# PFC_Method_Lighting_Driver_V2.net
KiCad netlist of a schematic drawn in EAGLE
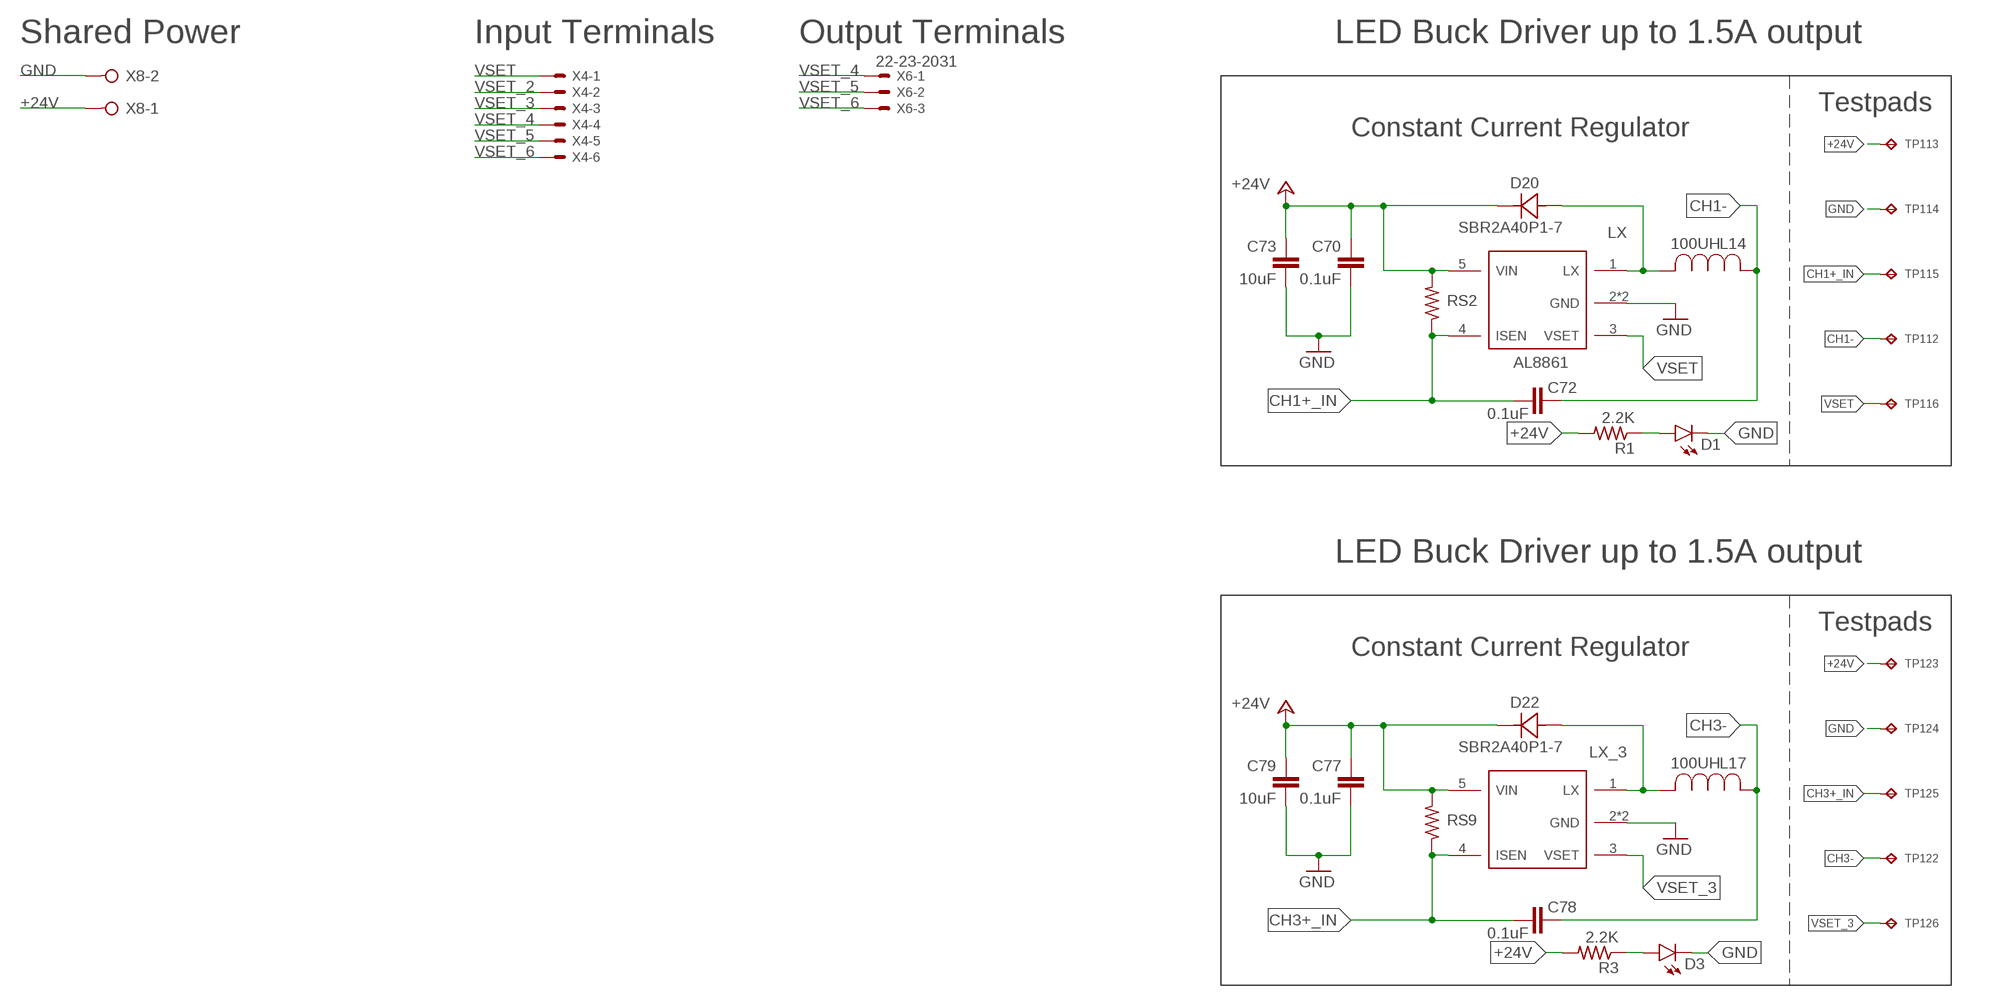
[diagram p0: schematic, sheet 1, part 1 of 2]
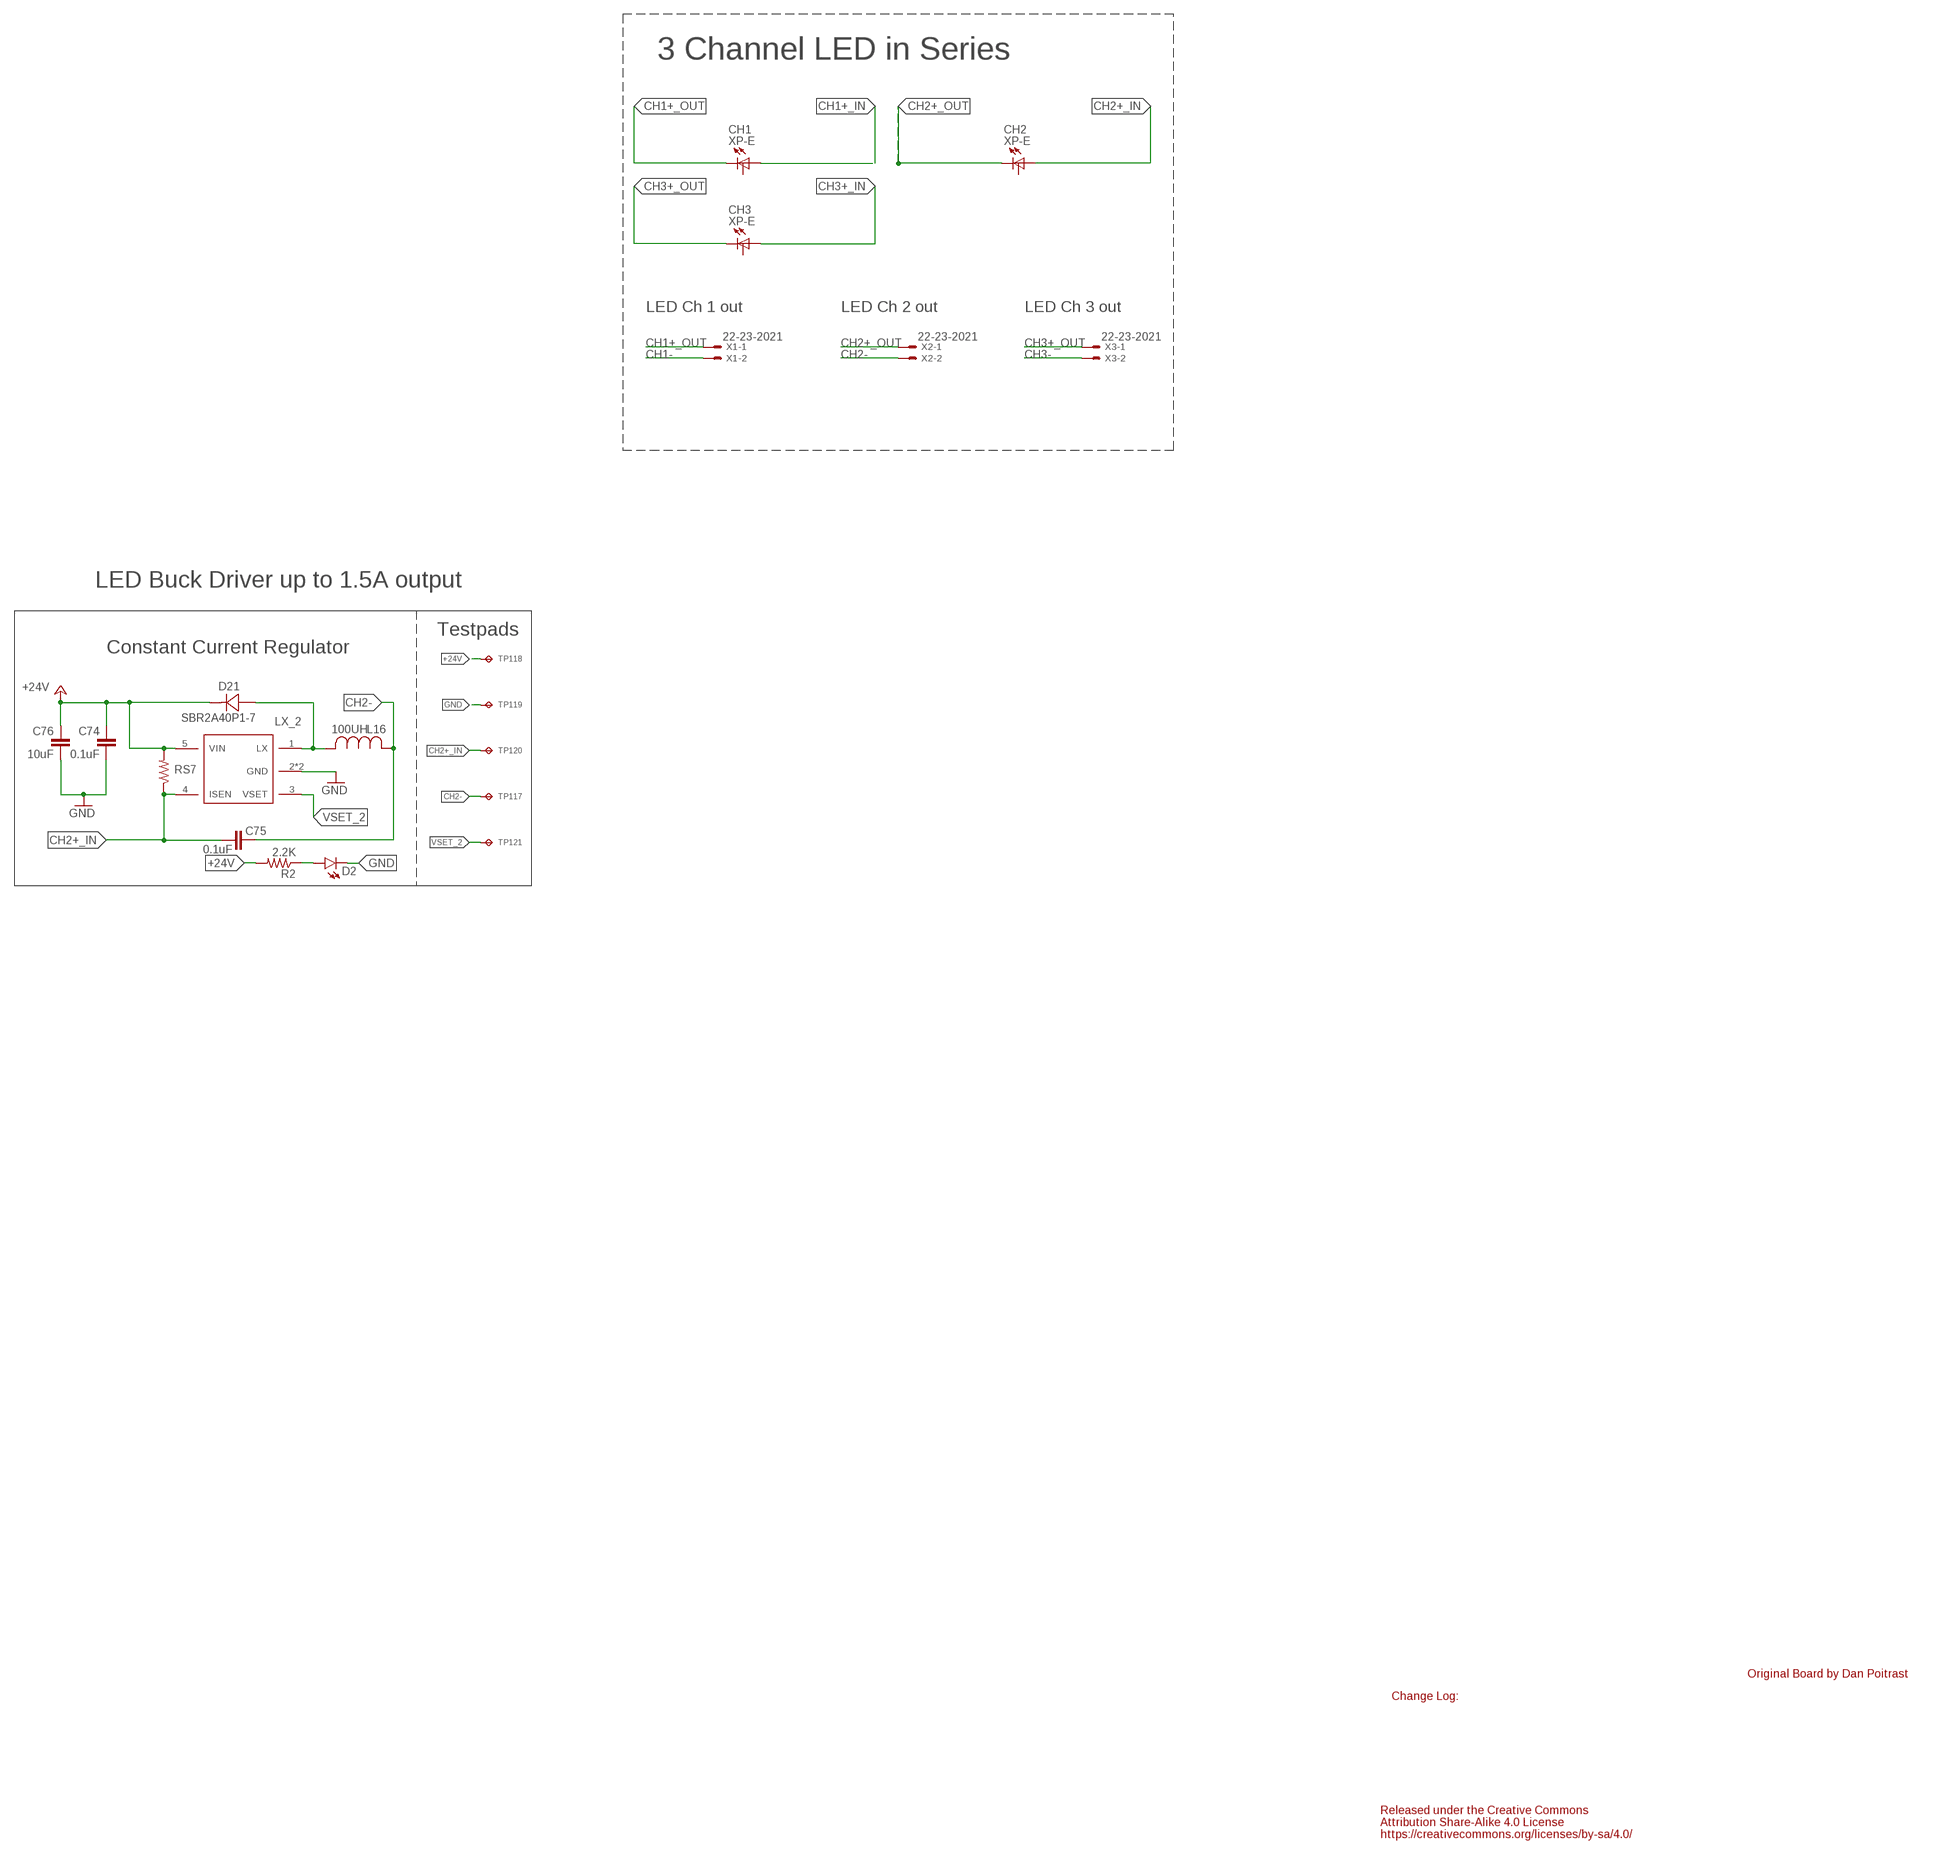
[diagram p1: schematic, sheet 1, part 2 of 2]

(export (version "E")
  (design (tool "Eeschema 10.0.6"))
  (components
    (comp (ref "C70")
      (value "0.1uF")
      (footprint "eagle-import:C0603")
      (fields (field (name "MANUFACTURER") "Kemet") (field (name "MPN") "C0603C104K5RACTU"))
      (libsource (lib "eagle-import") (part "0.1UF-C0603C104K5RACTU"))
    )
    (comp (ref "C72")
      (value "0.1uF")
      (footprint "eagle-import:C0603")
      (fields (field (name "MANUFACTURER") "Kemet") (field (name "MPN") "C0603C104K5RACTU"))
      (libsource (lib "eagle-import") (part "0.1UF-C0603C104K5RACTU"))
    )
    (comp (ref "C73")
      (value "10uF")
      (footprint "eagle-import:C0805")
      (fields (field (name "MANUFACTURER") "Taiyo Yuden") (field (name "MPN") "GMK212BBJ106KG-T"))
      (libsource (lib "eagle-import") (part "10UF-GMK212BBJ106KG-T"))
    )
    (comp (ref "C74")
      (value "0.1uF")
      (footprint "eagle-import:C0603")
      (fields (field (name "MANUFACTURER") "Kemet") (field (name "MPN") "C0603C104K5RACTU"))
      (libsource (lib "eagle-import") (part "0.1UF-C0603C104K5RACTU"))
    )
    (comp (ref "C75")
      (value "0.1uF")
      (footprint "eagle-import:C0603")
      (fields (field (name "MANUFACTURER") "Kemet") (field (name "MPN") "C0603C104K5RACTU"))
      (libsource (lib "eagle-import") (part "0.1UF-C0603C104K5RACTU"))
    )
    (comp (ref "C76")
      (value "10uF")
      (footprint "eagle-import:C0805")
      (fields (field (name "MANUFACTURER") "Taiyo Yuden") (field (name "MPN") "GMK212BBJ106KG-T"))
      (libsource (lib "eagle-import") (part "10UF-GMK212BBJ106KG-T"))
    )
    (comp (ref "C77")
      (value "0.1uF")
      (footprint "eagle-import:C0603")
      (fields (field (name "MANUFACTURER") "Kemet") (field (name "MPN") "C0603C104K5RACTU"))
      (libsource (lib "eagle-import") (part "0.1UF-C0603C104K5RACTU"))
    )
    (comp (ref "C78")
      (value "0.1uF")
      (footprint "eagle-import:C0603")
      (fields (field (name "MANUFACTURER") "Kemet") (field (name "MPN") "C0603C104K5RACTU"))
      (libsource (lib "eagle-import") (part "0.1UF-C0603C104K5RACTU"))
    )
    (comp (ref "C79")
      (value "10uF")
      (footprint "eagle-import:C0805")
      (fields (field (name "MANUFACTURER") "Taiyo Yuden") (field (name "MPN") "GMK212BBJ106KG-T"))
      (libsource (lib "eagle-import") (part "10UF-GMK212BBJ106KG-T"))
    )
    (comp (ref "CH1")
      (value "XP-E")
      (footprint "eagle-import:CREE-XLAMP-XP-E")
      (libsource (lib "eagle-import") (part "LED_W/THERM-XP-E"))
    )
    (comp (ref "CH2")
      (value "XP-E")
      (footprint "eagle-import:CREE-XLAMP-XP-E")
      (libsource (lib "eagle-import") (part "LED_W/THERM-XP-E"))
    )
    (comp (ref "CH3")
      (value "XP-E")
      (footprint "eagle-import:CREE-XLAMP-XP-E")
      (libsource (lib "eagle-import") (part "LED_W/THERM-XP-E"))
    )
    (comp (ref "D1")
      (value "LED5MM")
      (footprint "eagle-import:LED_5MM")
      (libsource (lib "eagle-import") (part "LED5MM"))
    )
    (comp (ref "D2")
      (value "LED5MM")
      (footprint "eagle-import:LED_5MM")
      (libsource (lib "eagle-import") (part "LED5MM"))
    )
    (comp (ref "D3")
      (value "LED5MM")
      (footprint "eagle-import:LED_5MM")
      (libsource (lib "eagle-import") (part "LED5MM"))
    )
    (comp (ref "D20")
      (value "SBR2A40P1-7")
      (footprint "eagle-import:POWERDI123")
      (fields (field (name "MANUFACTURER") "Diodes Incorporated"))
      (libsource (lib "eagle-import") (part "SBR2A40P1-7"))
    )
    (comp (ref "D21")
      (value "SBR2A40P1-7")
      (footprint "eagle-import:POWERDI123")
      (fields (field (name "MANUFACTURER") "Diodes Incorporated"))
      (libsource (lib "eagle-import") (part "SBR2A40P1-7"))
    )
    (comp (ref "D22")
      (value "SBR2A40P1-7")
      (footprint "eagle-import:POWERDI123")
      (fields (field (name "MANUFACTURER") "Diodes Incorporated"))
      (libsource (lib "eagle-import") (part "SBR2A40P1-7"))
    )
    (comp (ref "L14")
      (value "100UH")
      (footprint "eagle-import:IND_BOURNS_SDR1307")
      (libsource (lib "eagle-import") (part "100UH_BOURNES"))
    )
    (comp (ref "L16")
      (value "100UH")
      (footprint "eagle-import:IND_BOURNS_SDR1307")
      (libsource (lib "eagle-import") (part "100UH_BOURNES"))
    )
    (comp (ref "L17")
      (value "100UH")
      (footprint "eagle-import:IND_BOURNS_SDR1307")
      (libsource (lib "eagle-import") (part "100UH_BOURNES"))
    )
    (comp (ref "R1")
      (value "2.2K")
      (footprint "eagle-import:0207_10")
      (libsource (lib "eagle-import") (part "R-US_0207/10"))
    )
    (comp (ref "R2")
      (value "2.2K")
      (footprint "eagle-import:0207_10")
      (libsource (lib "eagle-import") (part "R-US_0207/10"))
    )
    (comp (ref "R3")
      (value "2.2K")
      (footprint "eagle-import:0207_10")
      (libsource (lib "eagle-import") (part "R-US_0207/10"))
    )
    (comp (ref "RS2")
      (value "6.34Ω")
      (footprint "eagle-import:R0805")
      (libsource (lib "eagle-import") (part "6.3OHM-RC0805FR-076R34L"))
    )
    (comp (ref "RS7")
      (value "6.34 Ω")
      (footprint "eagle-import:R0805")
      (libsource (lib "eagle-import") (part "6.3OHM-RC0805FR-076R34L"))
    )
    (comp (ref "RS9")
      (value "6.34 Ω")
      (footprint "eagle-import:R0805")
      (libsource (lib "eagle-import") (part "6.3OHM-RC0805FR-076R34L"))
    )
    (comp (ref "TP112")
      (value "TPTP06R")
      (footprint "eagle-import:TP06R")
      (libsource (lib "eagle-import") (part "TPTP06R"))
    )
    (comp (ref "TP113")
      (value "TPTP06R")
      (footprint "eagle-import:TP06R")
      (libsource (lib "eagle-import") (part "TPTP06R"))
    )
    (comp (ref "TP114")
      (value "TPTP06R")
      (footprint "eagle-import:TP06R")
      (libsource (lib "eagle-import") (part "TPTP06R"))
    )
    (comp (ref "TP115")
      (value "TPTP06R")
      (footprint "eagle-import:TP06R")
      (libsource (lib "eagle-import") (part "TPTP06R"))
    )
    (comp (ref "TP116")
      (value "TPTP06R")
      (footprint "eagle-import:TP06R")
      (libsource (lib "eagle-import") (part "TPTP06R"))
    )
    (comp (ref "TP117")
      (value "TPTP06R")
      (footprint "eagle-import:TP06R")
      (libsource (lib "eagle-import") (part "TPTP06R"))
    )
    (comp (ref "TP118")
      (value "TPTP06R")
      (footprint "eagle-import:TP06R")
      (libsource (lib "eagle-import") (part "TPTP06R"))
    )
    (comp (ref "TP119")
      (value "TPTP06R")
      (footprint "eagle-import:TP06R")
      (libsource (lib "eagle-import") (part "TPTP06R"))
    )
    (comp (ref "TP120")
      (value "TPTP06R")
      (footprint "eagle-import:TP06R")
      (libsource (lib "eagle-import") (part "TPTP06R"))
    )
    (comp (ref "TP121")
      (value "TPTP06R")
      (footprint "eagle-import:TP06R")
      (libsource (lib "eagle-import") (part "TPTP06R"))
    )
    (comp (ref "TP122")
      (value "TPTP06R")
      (footprint "eagle-import:TP06R")
      (libsource (lib "eagle-import") (part "TPTP06R"))
    )
    (comp (ref "TP123")
      (value "TPTP06R")
      (footprint "eagle-import:TP06R")
      (libsource (lib "eagle-import") (part "TPTP06R"))
    )
    (comp (ref "TP124")
      (value "TPTP06R")
      (footprint "eagle-import:TP06R")
      (libsource (lib "eagle-import") (part "TPTP06R"))
    )
    (comp (ref "TP125")
      (value "TPTP06R")
      (footprint "eagle-import:TP06R")
      (libsource (lib "eagle-import") (part "TPTP06R"))
    )
    (comp (ref "TP126")
      (value "TPTP06R")
      (footprint "eagle-import:TP06R")
      (libsource (lib "eagle-import") (part "TPTP06R"))
    )
    (comp (ref "U$25")
      (value "AL8861")
      (footprint "eagle-import:AL8861")
      (libsource (lib "eagle-import") (part "AL8861"))
    )
    (comp (ref "U$26")
      (value "AL8861")
      (footprint "eagle-import:AL8861")
      (libsource (lib "eagle-import") (part "AL8861"))
    )
    (comp (ref "U$27")
      (value "AL8861")
      (footprint "eagle-import:AL8861")
      (libsource (lib "eagle-import") (part "AL8861"))
    )
    (comp (ref "X1")
      (value "22-23-2021")
      (footprint "eagle-import:22-23-2021")
      (fields (field (name "MF") "MOLEX"))
      (libsource (lib "eagle-import") (part "22-23-2021"))
    )
    (comp (ref "X2")
      (value "22-23-2021")
      (footprint "eagle-import:22-23-2021")
      (fields (field (name "MF") "MOLEX"))
      (libsource (lib "eagle-import") (part "22-23-2021"))
    )
    (comp (ref "X3")
      (value "22-23-2021")
      (footprint "eagle-import:22-23-2021")
      (fields (field (name "MF") "MOLEX"))
      (libsource (lib "eagle-import") (part "22-23-2021"))
    )
    (comp (ref "X4")
      (value "22-23-2061")
      (footprint "eagle-import:22-23-2061")
      (fields (field (name "MF") "MOLEX"))
      (libsource (lib "eagle-import") (part "22-23-2061"))
    )
    (comp (ref "X6")
      (value "22-23-2031")
      (footprint "eagle-import:22-23-2031")
      (fields (field (name "MF") "MOLEX"))
      (libsource (lib "eagle-import") (part "22-23-2031"))
    )
    (comp (ref "X8")
      (value "W237-02P")
      (footprint "eagle-import:W237-132")
      (libsource (lib "eagle-import") (part "W237-02P"))
    )
  )
  (nets
    (net (code "1") (name "+24V") (class "Default")
      (node (ref "C70") (pin "1") (pinfunction "1_1") (pintype "passive"))
      (node (ref "C73") (pin "1") (pinfunction "1_1") (pintype "passive"))
      (node (ref "C74") (pin "1") (pinfunction "1_1") (pintype "passive"))
      (node (ref "C76") (pin "1") (pinfunction "1_1") (pintype "passive"))
      (node (ref "C77") (pin "1") (pinfunction "1_1") (pintype "passive"))
      (node (ref "C79") (pin "1") (pinfunction "1_1") (pintype "passive"))
      (node (ref "D20") (pin "-") (pinfunction "-_-") (pintype "passive"))
      (node (ref "D21") (pin "-") (pinfunction "-_-") (pintype "passive"))
      (node (ref "D22") (pin "-") (pinfunction "-_-") (pintype "passive"))
      (node (ref "R1") (pin "2") (pinfunction "2_2") (pintype "passive"))
      (node (ref "R2") (pin "2") (pinfunction "2_2") (pintype "passive"))
      (node (ref "R3") (pin "2") (pinfunction "2_2") (pintype "passive"))
      (node (ref "RS2") (pin "2") (pinfunction "2_2") (pintype "passive"))
      (node (ref "RS7") (pin "2") (pinfunction "2_2") (pintype "passive"))
      (node (ref "RS9") (pin "2") (pinfunction "2_2") (pintype "passive"))
      (node (ref "TP113") (pin "TP") (pinfunction "TP_TP") (pintype "input"))
      (node (ref "TP118") (pin "TP") (pinfunction "TP_TP") (pintype "input"))
      (node (ref "TP123") (pin "TP") (pinfunction "TP_TP") (pintype "input"))
      (node (ref "U$25") (pin "5") (pinfunction "VIN_5") (pintype "bidirectional"))
      (node (ref "U$26") (pin "5") (pinfunction "VIN_5") (pintype "bidirectional"))
      (node (ref "U$27") (pin "5") (pinfunction "VIN_5") (pintype "bidirectional"))
      (node (ref "X8") (pin "1") (pinfunction "KL_1") (pintype "passive"))
    )
    (net (code "2") (name "/LX") (class "Default")
      (node (ref "D20") (pin "+") (pinfunction "+_+") (pintype "passive"))
      (node (ref "L14") (pin "1") (pinfunction "1_1") (pintype "passive"))
      (node (ref "U$25") (pin "1") (pinfunction "LX_1") (pintype "bidirectional"))
    )
    (net (code "3") (name "/LX_2") (class "Default")
      (node (ref "D21") (pin "+") (pinfunction "+_+") (pintype "passive"))
      (node (ref "L16") (pin "1") (pinfunction "1_1") (pintype "passive"))
      (node (ref "U$26") (pin "1") (pinfunction "LX_1") (pintype "bidirectional"))
    )
    (net (code "4") (name "/LX_3") (class "Default")
      (node (ref "D22") (pin "+") (pinfunction "+_+") (pintype "passive"))
      (node (ref "L17") (pin "1") (pinfunction "1_1") (pintype "passive"))
      (node (ref "U$27") (pin "1") (pinfunction "LX_1") (pintype "bidirectional"))
    )
    (net (code "5") (name "/VSET_4") (class "Default")
      (node (ref "X4") (pin "4") (pinfunction "S_4") (pintype "passive"))
      (node (ref "X6") (pin "1") (pinfunction "S_1") (pintype "passive"))
    )
    (net (code "6") (name "/VSET_5") (class "Default")
      (node (ref "X4") (pin "5") (pinfunction "S_5") (pintype "passive"))
      (node (ref "X6") (pin "2") (pinfunction "S_2") (pintype "passive"))
    )
    (net (code "7") (name "/VSET_6") (class "Default")
      (node (ref "X4") (pin "6") (pinfunction "S_6") (pintype "passive"))
      (node (ref "X6") (pin "3") (pinfunction "S_3") (pintype "passive"))
    )
    (net (code "8") (name "CH1+_IN") (class "Default")
      (node (ref "C72") (pin "2") (pinfunction "2_2") (pintype "passive"))
      (node (ref "CH1") (pin "A") (pinfunction "A_A") (pintype "passive"))
      (node (ref "CH1") (pin "A@1") (pinfunction "A_A@1") (pintype "passive"))
      (node (ref "RS2") (pin "1") (pinfunction "1_1") (pintype "passive"))
      (node (ref "TP115") (pin "TP") (pinfunction "TP_TP") (pintype "input"))
      (node (ref "U$25") (pin "4") (pinfunction "ISEN_4") (pintype "bidirectional"))
    )
    (net (code "9") (name "CH1+_OUT") (class "Default")
      (node (ref "CH1") (pin "C") (pinfunction "C_C") (pintype "passive"))
      (node (ref "CH1") (pin "C@1") (pinfunction "C_C@1") (pintype "passive"))
      (node (ref "X1") (pin "1") (pinfunction "S_1") (pintype "passive"))
    )
    (net (code "10") (name "CH1-") (class "Default")
      (node (ref "C72") (pin "1") (pinfunction "1_1") (pintype "passive"))
      (node (ref "L14") (pin "2") (pinfunction "2_2") (pintype "passive"))
      (node (ref "TP112") (pin "TP") (pinfunction "TP_TP") (pintype "input"))
      (node (ref "X1") (pin "2") (pinfunction "S_2") (pintype "passive"))
    )
    (net (code "11") (name "CH2+_IN") (class "Default")
      (node (ref "C75") (pin "2") (pinfunction "2_2") (pintype "passive"))
      (node (ref "CH2") (pin "A") (pinfunction "A_A") (pintype "passive"))
      (node (ref "CH2") (pin "A@1") (pinfunction "A_A@1") (pintype "passive"))
      (node (ref "RS7") (pin "1") (pinfunction "1_1") (pintype "passive"))
      (node (ref "TP120") (pin "TP") (pinfunction "TP_TP") (pintype "input"))
      (node (ref "U$26") (pin "4") (pinfunction "ISEN_4") (pintype "bidirectional"))
    )
    (net (code "12") (name "CH2+_OUT") (class "Default")
      (node (ref "CH2") (pin "C") (pinfunction "C_C") (pintype "passive"))
      (node (ref "CH2") (pin "C@1") (pinfunction "C_C@1") (pintype "passive"))
      (node (ref "X2") (pin "1") (pinfunction "S_1") (pintype "passive"))
    )
    (net (code "13") (name "CH2-") (class "Default")
      (node (ref "C75") (pin "1") (pinfunction "1_1") (pintype "passive"))
      (node (ref "L16") (pin "2") (pinfunction "2_2") (pintype "passive"))
      (node (ref "TP117") (pin "TP") (pinfunction "TP_TP") (pintype "input"))
      (node (ref "X2") (pin "2") (pinfunction "S_2") (pintype "passive"))
    )
    (net (code "14") (name "CH3+_IN") (class "Default")
      (node (ref "C78") (pin "2") (pinfunction "2_2") (pintype "passive"))
      (node (ref "CH3") (pin "A") (pinfunction "A_A") (pintype "passive"))
      (node (ref "CH3") (pin "A@1") (pinfunction "A_A@1") (pintype "passive"))
      (node (ref "RS9") (pin "1") (pinfunction "1_1") (pintype "passive"))
      (node (ref "TP125") (pin "TP") (pinfunction "TP_TP") (pintype "input"))
      (node (ref "U$27") (pin "4") (pinfunction "ISEN_4") (pintype "bidirectional"))
    )
    (net (code "15") (name "CH3+_OUT") (class "Default")
      (node (ref "CH3") (pin "C") (pinfunction "C_C") (pintype "passive"))
      (node (ref "CH3") (pin "C@1") (pinfunction "C_C@1") (pintype "passive"))
      (node (ref "X3") (pin "1") (pinfunction "S_1") (pintype "passive"))
    )
    (net (code "16") (name "CH3-") (class "Default")
      (node (ref "C78") (pin "1") (pinfunction "1_1") (pintype "passive"))
      (node (ref "L17") (pin "2") (pinfunction "2_2") (pintype "passive"))
      (node (ref "TP122") (pin "TP") (pinfunction "TP_TP") (pintype "input"))
      (node (ref "X3") (pin "2") (pinfunction "S_2") (pintype "passive"))
    )
    (net (code "17") (name "GND") (class "Default")
      (node (ref "C70") (pin "2") (pinfunction "2_2") (pintype "passive"))
      (node (ref "C73") (pin "2") (pinfunction "2_2") (pintype "passive"))
      (node (ref "C74") (pin "2") (pinfunction "2_2") (pintype "passive"))
      (node (ref "C76") (pin "2") (pinfunction "2_2") (pintype "passive"))
      (node (ref "C77") (pin "2") (pinfunction "2_2") (pintype "passive"))
      (node (ref "C79") (pin "2") (pinfunction "2_2") (pintype "passive"))
      (node (ref "D1") (pin "K") (pinfunction "C_K") (pintype "passive"))
      (node (ref "D2") (pin "K") (pinfunction "C_K") (pintype "passive"))
      (node (ref "D3") (pin "K") (pinfunction "C_K") (pintype "passive"))
      (node (ref "TP114") (pin "TP") (pinfunction "TP_TP") (pintype "input"))
      (node (ref "TP119") (pin "TP") (pinfunction "TP_TP") (pintype "input"))
      (node (ref "TP124") (pin "TP") (pinfunction "TP_TP") (pintype "input"))
      (node (ref "U$25") (pin "2") (pinfunction "GND_2") (pintype "bidirectional"))
      (node (ref "U$25") (pin "44") (pinfunction "GND_44") (pintype "bidirectional"))
      (node (ref "U$26") (pin "2") (pinfunction "GND_2") (pintype "bidirectional"))
      (node (ref "U$26") (pin "44") (pinfunction "GND_44") (pintype "bidirectional"))
      (node (ref "U$27") (pin "2") (pinfunction "GND_2") (pintype "bidirectional"))
      (node (ref "U$27") (pin "44") (pinfunction "GND_44") (pintype "bidirectional"))
      (node (ref "X8") (pin "2") (pinfunction "KL_2") (pintype "passive"))
    )
    (net (code "18") (name "Net-(D1-PadA)") (class "Default")
      (node (ref "D1") (pin "A") (pinfunction "A_A") (pintype "passive"))
      (node (ref "R1") (pin "1") (pinfunction "1_1") (pintype "passive"))
    )
    (net (code "19") (name "Net-(D2-PadA)") (class "Default")
      (node (ref "D2") (pin "A") (pinfunction "A_A") (pintype "passive"))
      (node (ref "R2") (pin "1") (pinfunction "1_1") (pintype "passive"))
    )
    (net (code "20") (name "Net-(D3-PadA)") (class "Default")
      (node (ref "D3") (pin "A") (pinfunction "A_A") (pintype "passive"))
      (node (ref "R3") (pin "1") (pinfunction "1_1") (pintype "passive"))
    )
    (net (code "21") (name "VSET") (class "Default")
      (node (ref "TP116") (pin "TP") (pinfunction "TP_TP") (pintype "input"))
      (node (ref "U$25") (pin "3") (pinfunction "VSET_3") (pintype "bidirectional"))
      (node (ref "X4") (pin "1") (pinfunction "S_1") (pintype "passive"))
    )
    (net (code "22") (name "VSET_2") (class "Default")
      (node (ref "TP121") (pin "TP") (pinfunction "TP_TP") (pintype "input"))
      (node (ref "U$26") (pin "3") (pinfunction "VSET_3") (pintype "bidirectional"))
      (node (ref "X4") (pin "2") (pinfunction "S_2") (pintype "passive"))
    )
    (net (code "23") (name "VSET_3") (class "Default")
      (node (ref "TP126") (pin "TP") (pinfunction "TP_TP") (pintype "input"))
      (node (ref "U$27") (pin "3") (pinfunction "VSET_3") (pintype "bidirectional"))
      (node (ref "X4") (pin "3") (pinfunction "S_3") (pintype "passive"))
    )
    (net (code "24") (name "unconnected-(CH1-PadTHERM)") (class "Default")
      (node (ref "CH1") (pin "THERM") (pinfunction "THERM_THERM") (pintype "bidirectional"))
    )
    (net (code "25") (name "unconnected-(CH2-PadTHERM)") (class "Default")
      (node (ref "CH2") (pin "THERM") (pinfunction "THERM_THERM") (pintype "bidirectional"))
    )
    (net (code "26") (name "unconnected-(CH3-PadTHERM)") (class "Default")
      (node (ref "CH3") (pin "THERM") (pinfunction "THERM_THERM") (pintype "bidirectional"))
    )
  )
)
